# LC_EXT_SCH.net
KiCad netlist of a schematic drawn in Altium Designer
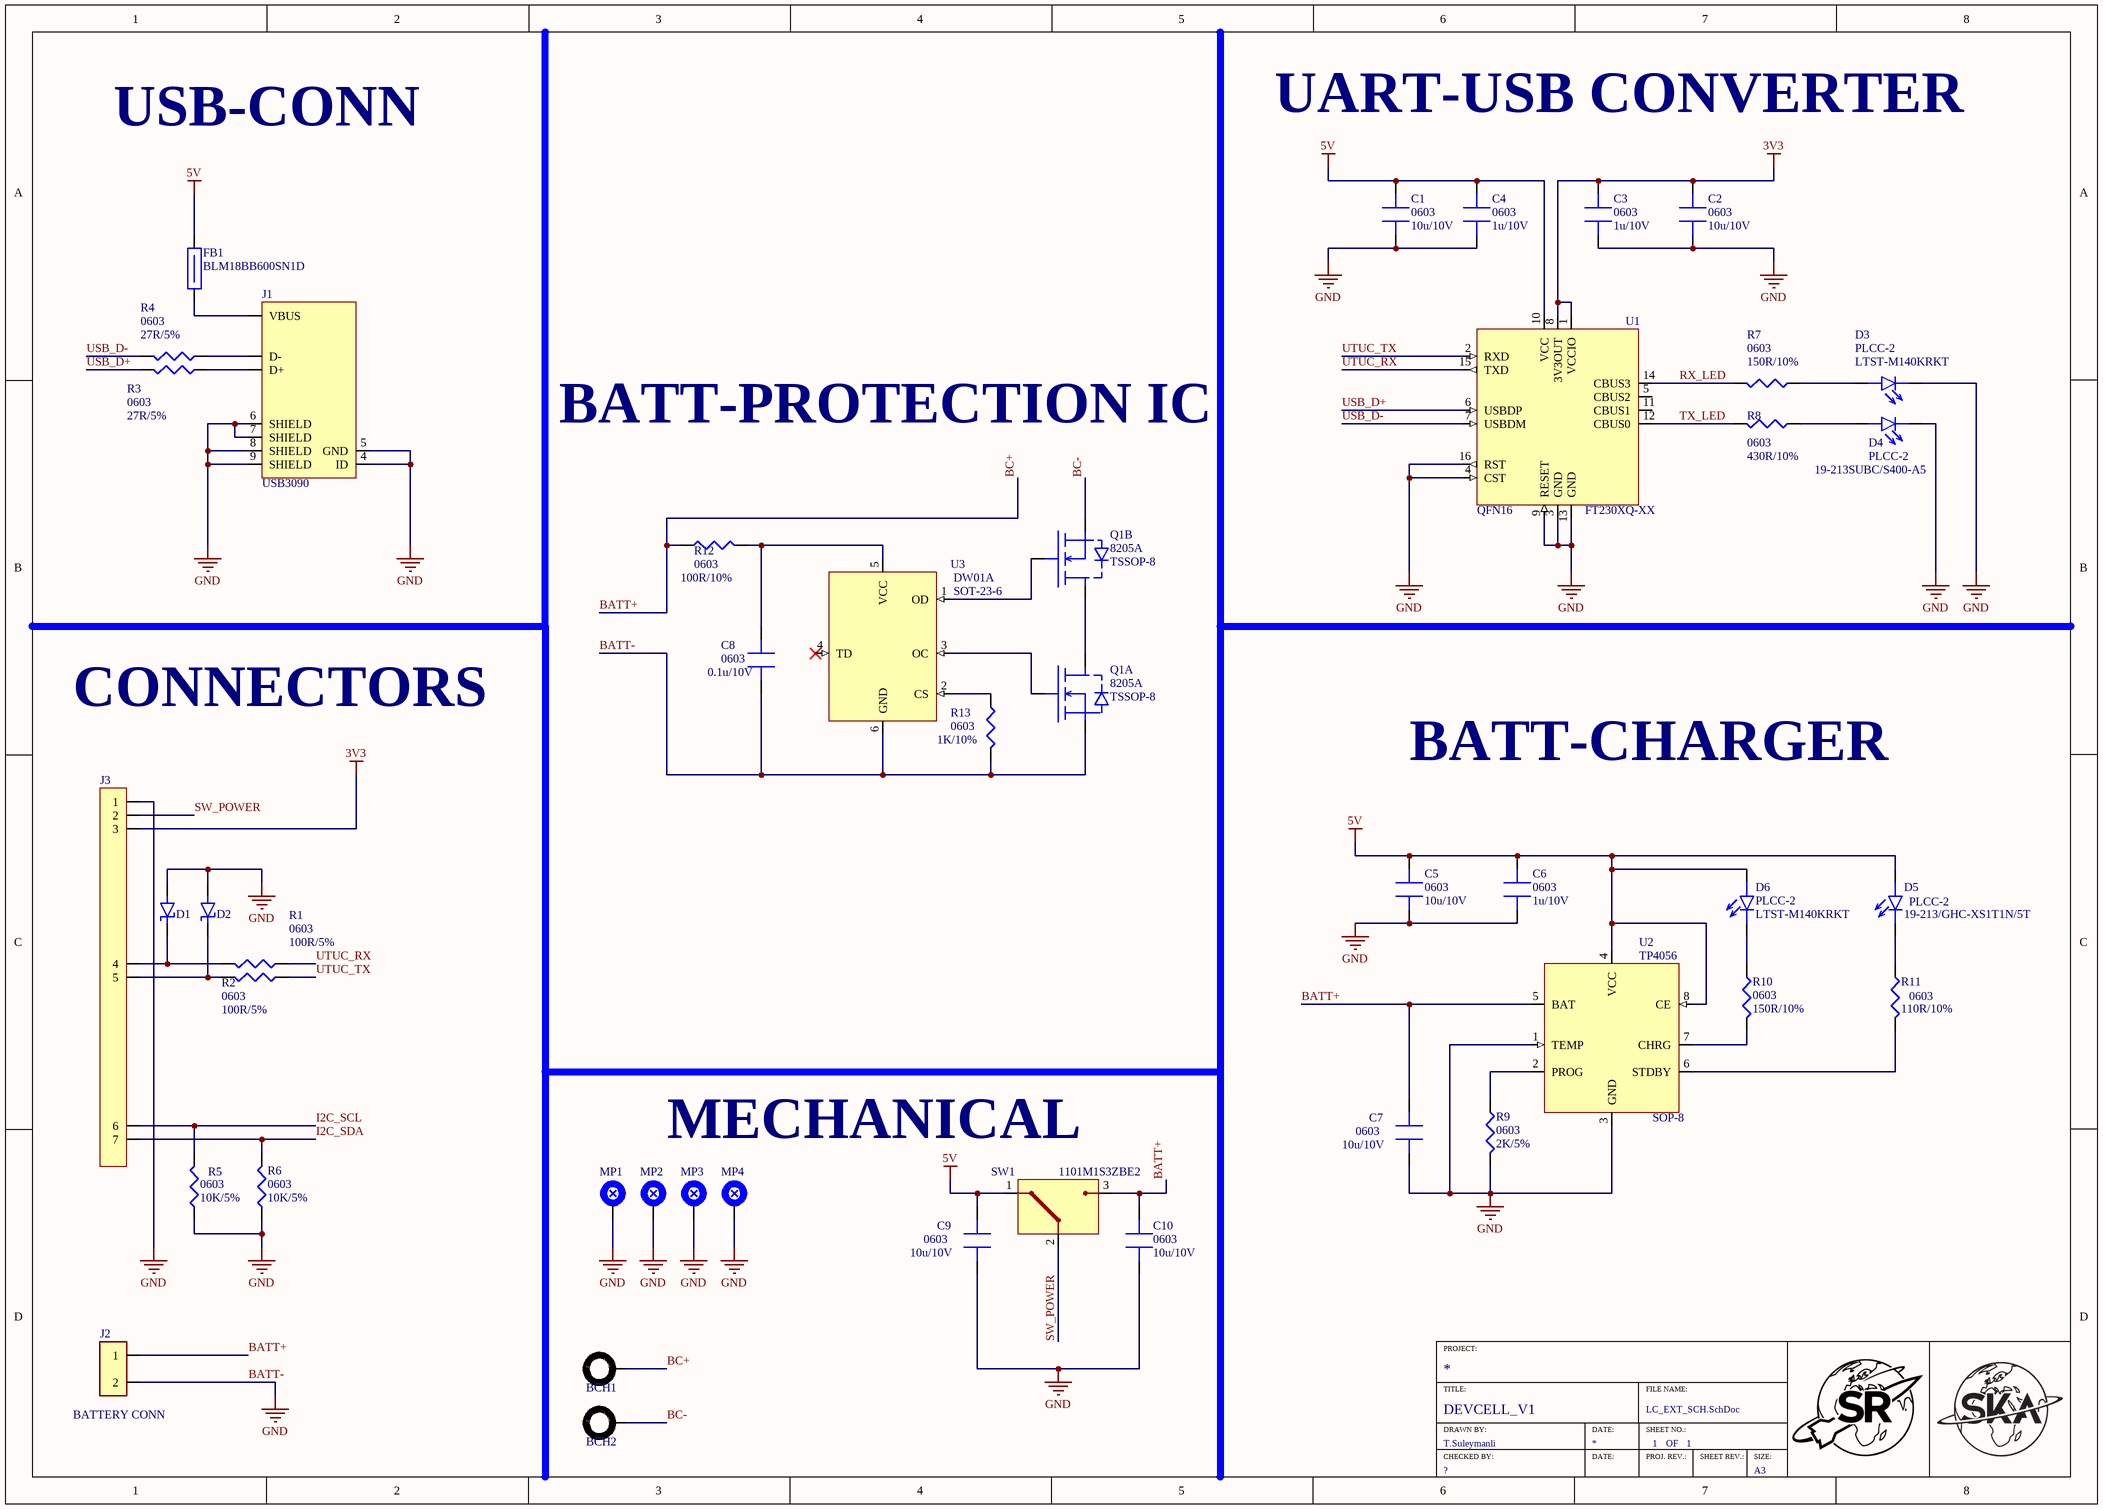
[diagram p0: LC_EXT_SCH.SchDoc]

(export (version "E")
  (design (tool "Eeschema 10.0.6"))
  (components
    (comp (ref "BCH1")
      (value "BATTERY_CONNECTION_HOLE")
      (footprint "BATTERY_CONN_HOLE")
      (description "Pin hole for battery connection")
      (libsource (lib "LC_EXT_S_lib") (part "BATTERY_CONNECTION_HOLE"))
    )
    (comp (ref "BCH2")
      (value "BATTERY_CONNECTION_HOLE")
      (footprint "BATTERY_CONN_HOLE")
      (description "Pin hole for battery connection")
      (libsource (lib "LC_EXT_S_lib") (part "BATTERY_CONNECTION_HOLE"))
    )
    (comp (ref "C1")
      (value "10u/10V")
      (footprint "CAPC1005X06L [0402]")
      (description "Standard capacitor")
      (fields (field (name "PACKAGE") "0603") (field (name "Comment") "C"))
      (libsource (lib "SR_Library") (part "C"))
    )
    (comp (ref "C2")
      (value "10u/10V")
      (footprint "CAPC1005X06L [0402]")
      (description "Standard capacitor")
      (fields (field (name "PACKAGE") "0603") (field (name "Comment") "C"))
      (libsource (lib "SR_Library") (part "C"))
    )
    (comp (ref "C3")
      (value "1u/10V")
      (footprint "CAPC1005X06L [0402]")
      (description "Standard capacitor")
      (fields (field (name "PACKAGE") "0603") (field (name "Comment") "C"))
      (libsource (lib "SR_Library") (part "C"))
    )
    (comp (ref "C4")
      (value "1u/10V")
      (footprint "CAPC1005X06L [0402]")
      (description "Standard capacitor")
      (fields (field (name "PACKAGE") "0603") (field (name "Comment") "C"))
      (libsource (lib "SR_Library") (part "C"))
    )
    (comp (ref "C5")
      (value "10u/10V")
      (footprint "CAPC1005X06L [0402]")
      (description "Standard capacitor")
      (fields (field (name "PACKAGE") "0603") (field (name "Comment") "C"))
      (libsource (lib "SR_Library") (part "C"))
    )
    (comp (ref "C6")
      (value "1u/10V")
      (footprint "CAPC1005X06L [0402]")
      (description "Standard capacitor")
      (fields (field (name "PACKAGE") "0603") (field (name "Comment") "C"))
      (libsource (lib "SR_Library") (part "C"))
    )
    (comp (ref "C7")
      (value "10u/10V")
      (footprint "CAPC1005X06L [0402]")
      (description "Standard capacitor")
      (fields (field (name "PACKAGE") "0603") (field (name "Comment") "C"))
      (libsource (lib "SR_Library") (part "C"))
    )
    (comp (ref "C8")
      (value "0.1u/10V")
      (footprint "CAPC1005X06L [0402]")
      (description "Standard capacitor")
      (fields (field (name "PACKAGE") "0603") (field (name "Comment") "C"))
      (libsource (lib "SR_Library") (part "C"))
    )
    (comp (ref "C9")
      (value "10u/10V")
      (footprint "CAPC1005X06L [0402]")
      (description "Standard capacitor")
      (fields (field (name "PACKAGE") "0603") (field (name "Comment") "C"))
      (libsource (lib "SR_Library") (part "C"))
    )
    (comp (ref "C10")
      (value "10u/10V")
      (footprint "CAPC1005X06L [0402]")
      (description "Standard capacitor")
      (fields (field (name "PACKAGE") "0603") (field (name "Comment") "C"))
      (libsource (lib "SR_Library") (part "C"))
    )
    (comp (ref "D1")
      (value "ESD5Z2.5T1G")
      (footprint "SODFL160X60-2N")
      (description "ESD protection diode, 4V")
      (libsource (lib "LC_EXT_S_lib") (part "D_Zener"))
    )
    (comp (ref "D2")
      (value "ESD5Z2.5T1G")
      (footprint "SODFL160X60-2N")
      (description "ESD protection diode, 4V")
      (libsource (lib "LC_EXT_S_lib") (part "D_Zener"))
    )
    (comp (ref "D3")
      (value "LTST-M140KRKT")
      (footprint "LEDC1608X35N")
      (description "LED; SMD; 3014; red; 0.24÷0.84lm; 90÷280mcd; 3x1.4x1.2mm; 120°; 20mA")
      (fields (field (name "PACKAGE") "PLCC-2") (field (name "PN") "LTST-M140KRKT"))
      (libsource (lib "SR_Library") (part "sLED"))
    )
    (comp (ref "D4")
      (value "19-213SUBC/S400-A5/S208-2/TR8")
      (footprint "19-213/GHC-XS1T1N/5T")
      (description "LED; SMD; blue; 10÷32mcd; 1.6x0.8x0.6mm; 120°; 2.7÷3.1V; 5mA; 40mW")
      (fields (field (name "PACKAGE") "PLCC-2") (field (name "PN") "19-213SUBC/S400-A5"))
      (libsource (lib "SR_Library") (part "sLED"))
    )
    (comp (ref "D5")
      (value "19-213/GHC-XS1T1N/5T")
      (footprint "19-213/GHC-XS1T1N/5T")
      (description "LED; SMD; 1608; green; 180÷360mcd; 1.6x0.8x0.6mm; 120°; 2.7÷3.7V")
      (fields (field (name "PACKAGE") "PLCC-2") (field (name "PN") "19-213/GHC-XS1T1N/5T"))
      (libsource (lib "SR_Library") (part "sLED"))
    )
    (comp (ref "D6")
      (value "LTST-M140KRKT")
      (footprint "LEDC1608X35N")
      (description "LED; SMD; 3014; red; 0.24÷0.84lm; 90÷280mcd; 3x1.4x1.2mm; 120°; 20mA")
      (fields (field (name "PACKAGE") "PLCC-2") (field (name "PN") "LTST-M140KRKT"))
      (libsource (lib "SR_Library") (part "sLED"))
    )
    (comp (ref "FB1")
      (value "BLM18BB600SN1D")
      (footprint "BEADC1608X95N")
      (description "Ferrite: bead; Imp.@ 100MHz: 60Ω; SMD; 0.55A; 0603; R: 0.25Ω")
      (libsource (lib "LC_EXT_S_lib") (part "Ferrite Bead"))
    )
    (comp (ref "J1")
      (value "USB3090")
      (footprint "USB3090-2888209")
      (description "USB Connectors Micro A/B Skt,Bottom-SMT, R/A, 30u No Peg, W/shell stake,T&R")
      (libsource (lib "LC_EXT_S_lib") (part "USB3090-30-A"))
    )
    (comp (ref "J2")
      (value "BATTERY CONN")
      (footprint "DG30825402P1400AH")
      (description "Standard battery connector for Li Ion battery")
      (libsource (lib "LC_EXT_S_lib") (part "BATTERY CONN"))
    )
    (comp (ref "J3")
      (value "Female_Header x7")
      (footprint "Female Header")
      (description "Header connectors x7 with 2.54 pitch")
      (libsource (lib "LC_EXT_S_lib") (part "Female_Header"))
    )
    (comp (ref "MP1")
      (value "Mounting hole")
      (footprint "Mounting_hole_M3")
      (libsource (lib "SR_Library") (part "Mounting hole"))
    )
    (comp (ref "MP2")
      (value "Mounting hole")
      (footprint "Mounting_hole_M3")
      (libsource (lib "SR_Library") (part "Mounting hole"))
    )
    (comp (ref "MP3")
      (value "Mounting hole")
      (footprint "Mounting_hole_M3")
      (libsource (lib "SR_Library") (part "Mounting hole"))
    )
    (comp (ref "MP4")
      (value "Mounting hole")
      (footprint "Mounting_hole_M3")
      (libsource (lib "SR_Library") (part "Mounting hole"))
    )
    (comp (ref "Q1")
      (value "8205A")
      (footprint "TSOP65P610X120-8M")
      (fields (field (name "PACKAGE") "TSSOP-8"))
      (libsource (lib "") (part "8205A_1"))
    )
    (comp (ref "R1")
      (value "100R/5%")
      (footprint "RESC1005X04L [0402]")
      (description "Standard resistor")
      (fields (field (name "PACKAGE") "0603") (field (name "Comment") "R"))
      (libsource (lib "SR_Library") (part "R"))
    )
    (comp (ref "R2")
      (value "100R/5%")
      (footprint "RESC1005X04L [0402]")
      (description "Standard resistor")
      (fields (field (name "PACKAGE") "0603") (field (name "Comment") "R"))
      (libsource (lib "SR_Library") (part "R"))
    )
    (comp (ref "R3")
      (value "27R/5%")
      (footprint "RESC1005X04L [0402]")
      (description "Standard resistor")
      (fields (field (name "PACKAGE") "0603") (field (name "Comment") "R"))
      (libsource (lib "SR_Library") (part "R"))
    )
    (comp (ref "R4")
      (value "27R/5%")
      (footprint "RESC1005X04L [0402]")
      (description "Standard resistor")
      (fields (field (name "PACKAGE") "0603") (field (name "Comment") "R"))
      (libsource (lib "SR_Library") (part "R"))
    )
    (comp (ref "R5")
      (value "10K/5%")
      (footprint "RESC1608X06M[0603]")
      (description "Standard resistor")
      (fields (field (name "PACKAGE") "0603") (field (name "Comment") "R"))
      (libsource (lib "SR_Library") (part "R"))
    )
    (comp (ref "R6")
      (value "10K/5%")
      (footprint "RESC1608X06M[0603]")
      (description "Standard resistor")
      (fields (field (name "PACKAGE") "0603") (field (name "Comment") "R"))
      (libsource (lib "SR_Library") (part "R"))
    )
    (comp (ref "R7")
      (value "150R/10%")
      (footprint "RESC1005X04L [0402]")
      (description "Standard resistor")
      (fields (field (name "PACKAGE") "0603") (field (name "Comment") "R"))
      (libsource (lib "SR_Library") (part "R"))
    )
    (comp (ref "R8")
      (value "430R/10%")
      (footprint "RESC1005X04L [0402]")
      (description "Standard resistor")
      (fields (field (name "PACKAGE") "0603") (field (name "Comment") "R"))
      (libsource (lib "SR_Library") (part "R"))
    )
    (comp (ref "R9")
      (value "2K/5%")
      (footprint "RESC1005X04L [0402]")
      (description "Standard resistor")
      (fields (field (name "PACKAGE") "0603") (field (name "Comment") "R"))
      (libsource (lib "SR_Library") (part "R"))
    )
    (comp (ref "R10")
      (value "150R/10%")
      (footprint "RESC1005X04L [0402]")
      (description "Standard resistor")
      (fields (field (name "PACKAGE") "0603") (field (name "Comment") "R"))
      (libsource (lib "SR_Library") (part "R"))
    )
    (comp (ref "R11")
      (value "110R/10%")
      (footprint "RESC1005X04L [0402]")
      (description "Standard resistor")
      (fields (field (name "PACKAGE") "0603") (field (name "Comment") "R"))
      (libsource (lib "SR_Library") (part "R"))
    )
    (comp (ref "R12")
      (value "100R/10%")
      (footprint "RESC1005X04L [0402]")
      (description "Standard resistor")
      (fields (field (name "PACKAGE") "0603") (field (name "Comment") "R"))
      (libsource (lib "SR_Library") (part "R"))
    )
    (comp (ref "R13")
      (value "1K/10%")
      (footprint "RESC1005X04L [0402]")
      (description "Standard resistor")
      (fields (field (name "PACKAGE") "0603") (field (name "Comment") "R"))
      (libsource (lib "SR_Library") (part "R"))
    )
    (comp (ref "SW1")
      (value "1101M1S3ZBE2")
      (footprint "1101M1S3ZBE2")
      (description "Switch: slide; Pos: 2; SPDT; 0.02A/20VAC; 0.02A/20VDC; ON-ON; 1000")
      (libsource (lib "LC_EXT_S_lib") (part "1101M1S3ZBE2"))
    )
    (comp (ref "U1")
      (value "FT230XQ-XX")
      (footprint "QFN65P400X400X75_HS-17N")
      (description "USB Interface IC USB to Basic Serial UART IC QFN-16")
      (fields (field (name "PACKAGE") "QFN16"))
      (libsource (lib "LC_EXT_S_lib") (part "FT230XQ-T"))
    )
    (comp (ref "U2")
      (value "TP4056")
      (footprint "SOP127P600X170-8N")
      (description "1A Standalone Linear Li-lon Battery Charger with Thermal\r\nRegulation")
      (fields (field (name "PACKAGE") "SOP-8"))
      (libsource (lib "LC_EXT_S_lib") (part "TP4056-42-SOP8-PP"))
    )
    (comp (ref "U3")
      (value "DW01A")
      (footprint "SOT95P270X145-6M")
      (description "Battery protection IC, SOT-23-6, 4.3V± 50mV, -40°C ~ +85°C")
      (fields (field (name "PACKAGE") "SOT-23-6"))
      (libsource (lib "LC_EXT_S_lib") (part "DW01A"))
    )
  )
  (nets
    (net (code "1") (name "/BATT+") (class "Default")
      (node (ref "BCH1") (pin "1") (pinfunction "1_1") (pintype "passive"))
      (node (ref "C10") (pin "1") (pinfunction "1_1") (pintype "passive"))
      (node (ref "C7") (pin "1") (pinfunction "1_1") (pintype "passive"))
      (node (ref "J2") (pin "1") (pinfunction "1_1") (pintype "passive"))
      (node (ref "R12") (pin "2") (pinfunction "2_2") (pintype "passive"))
      (node (ref "SW1") (pin "3") (pinfunction "BATT+_3") (pintype "passive"))
      (node (ref "U2") (pin "5") (pinfunction "BAT_5") (pintype "passive"))
    )
    (net (code "2") (name "/BC-") (class "Default")
      (node (ref "BCH2") (pin "1") (pinfunction "1_1") (pintype "passive"))
      (node (ref "Q1") (pin "7") (pinfunction "S2_7") (pintype "passive"))
    )
    (net (code "3") (name "/I2C_SCL") (class "Default")
      (node (ref "J3") (pin "6") (pinfunction "6_6") (pintype "passive"))
      (node (ref "R5") (pin "1") (pinfunction "1_1") (pintype "passive"))
    )
    (net (code "4") (name "/I2C_SDA") (class "Default")
      (node (ref "J3") (pin "7") (pinfunction "7_7") (pintype "passive"))
      (node (ref "R6") (pin "1") (pinfunction "1_1") (pintype "passive"))
    )
    (net (code "5") (name "/RX_LED") (class "Default")
      (node (ref "R7") (pin "1") (pinfunction "1_1") (pintype "passive"))
      (node (ref "U1") (pin "14") (pinfunction "CBUS3_14") (pintype "bidirectional"))
    )
    (net (code "6") (name "/SW_POWER") (class "Default")
      (node (ref "J3") (pin "2") (pinfunction "2_2") (pintype "passive"))
      (node (ref "SW1") (pin "2") (pinfunction "COM_2") (pintype "passive"))
    )
    (net (code "7") (name "/TX_LED") (class "Default")
      (node (ref "R8") (pin "1") (pinfunction "1_1") (pintype "passive"))
      (node (ref "U1") (pin "12") (pinfunction "CBUS0_12") (pintype "bidirectional"))
    )
    (net (code "8") (name "/USB_D+") (class "Default")
      (node (ref "R3") (pin "1") (pinfunction "1_1") (pintype "passive"))
      (node (ref "U1") (pin "6") (pinfunction "USBDP_6") (pintype "input"))
    )
    (net (code "9") (name "/USB_D-") (class "Default")
      (node (ref "R4") (pin "1") (pinfunction "1_1") (pintype "passive"))
      (node (ref "U1") (pin "7") (pinfunction "USBDM_7") (pintype "input"))
    )
    (net (code "10") (name "/UTUC_RX") (class "Default")
      (node (ref "R1") (pin "2") (pinfunction "2_2") (pintype "passive"))
      (node (ref "U1") (pin "15") (pinfunction "TXD_15") (pintype "output"))
    )
    (net (code "11") (name "/UTUC_TX") (class "Default")
      (node (ref "R2") (pin "2") (pinfunction "2_2") (pintype "passive"))
      (node (ref "U1") (pin "2") (pinfunction "RXD_2") (pintype "input"))
    )
    (net (code "12") (name "3V3") (class "Default")
      (node (ref "C2") (pin "1") (pinfunction "1_1") (pintype "passive"))
      (node (ref "C3") (pin "1") (pinfunction "1_1") (pintype "passive"))
      (node (ref "J3") (pin "3") (pinfunction "3_3") (pintype "passive"))
      (node (ref "U1") (pin "1") (pinfunction "VCCIO_1") (pintype "passive"))
      (node (ref "U1") (pin "8") (pinfunction "3V3OUT_8") (pintype "passive"))
    )
    (net (code "13") (name "5V") (class "Default")
      (node (ref "C1") (pin "1") (pinfunction "1_1") (pintype "passive"))
      (node (ref "C4") (pin "1") (pinfunction "1_1") (pintype "passive"))
      (node (ref "C5") (pin "1") (pinfunction "1_1") (pintype "passive"))
      (node (ref "C6") (pin "1") (pinfunction "1_1") (pintype "passive"))
      (node (ref "C9") (pin "1") (pinfunction "1_1") (pintype "passive"))
      (node (ref "D5") (pin "2") (pinfunction "2_2") (pintype "passive"))
      (node (ref "D6") (pin "2") (pinfunction "2_2") (pintype "passive"))
      (node (ref "FB1") (pin "2") (pinfunction "2_2") (pintype "passive"))
      (node (ref "SW1") (pin "1") (pinfunction "5V_1") (pintype "passive"))
      (node (ref "U1") (pin "10") (pinfunction "VCC_10") (pintype "passive"))
      (node (ref "U2") (pin "4") (pinfunction "VCC_4") (pintype "passive"))
      (node (ref "U2") (pin "8") (pinfunction "CE_8") (pintype "input"))
    )
    (net (code "14") (name "GND") (class "Default")
      (node (ref "C1") (pin "2") (pinfunction "2_2") (pintype "passive"))
      (node (ref "C10") (pin "2") (pinfunction "2_2") (pintype "passive"))
      (node (ref "C2") (pin "2") (pinfunction "2_2") (pintype "passive"))
      (node (ref "C3") (pin "2") (pinfunction "2_2") (pintype "passive"))
      (node (ref "C4") (pin "2") (pinfunction "2_2") (pintype "passive"))
      (node (ref "C5") (pin "2") (pinfunction "2_2") (pintype "passive"))
      (node (ref "C6") (pin "2") (pinfunction "2_2") (pintype "passive"))
      (node (ref "C7") (pin "2") (pinfunction "2_2") (pintype "passive"))
      (node (ref "C8") (pin "2") (pinfunction "2_2") (pintype "passive"))
      (node (ref "C9") (pin "2") (pinfunction "2_2") (pintype "passive"))
      (node (ref "D1") (pin "2") (pinfunction "A_2") (pintype "passive"))
      (node (ref "D2") (pin "2") (pinfunction "A_2") (pintype "passive"))
      (node (ref "D3") (pin "1") (pinfunction "1_1") (pintype "passive"))
      (node (ref "D4") (pin "1") (pinfunction "1_1") (pintype "passive"))
      (node (ref "J1") (pin "4") (pinfunction "ID_4") (pintype "passive"))
      (node (ref "J1") (pin "5") (pinfunction "GND_5") (pintype "passive"))
      (node (ref "J1") (pin "6") (pinfunction "SHIELD_6") (pintype "passive"))
      (node (ref "J1") (pin "7") (pinfunction "SHIELD_7") (pintype "passive"))
      (node (ref "J1") (pin "8") (pinfunction "SHIELD_8") (pintype "passive"))
      (node (ref "J1") (pin "9") (pinfunction "SHIELD_9") (pintype "passive"))
      (node (ref "J2") (pin "2") (pinfunction "2_2") (pintype "passive"))
      (node (ref "J3") (pin "1") (pinfunction "1_1") (pintype "passive"))
      (node (ref "MP1") (pin "1") (pinfunction "1_1") (pintype "passive"))
      (node (ref "MP2") (pin "1") (pinfunction "1_1") (pintype "passive"))
      (node (ref "MP3") (pin "1") (pinfunction "1_1") (pintype "passive"))
      (node (ref "MP4") (pin "1") (pinfunction "1_1") (pintype "passive"))
      (node (ref "Q1") (pin "2") (pinfunction "S1_2") (pintype "passive"))
      (node (ref "R13") (pin "1") (pinfunction "1_1") (pintype "passive"))
      (node (ref "R5") (pin "2") (pinfunction "2_2") (pintype "passive"))
      (node (ref "R6") (pin "2") (pinfunction "2_2") (pintype "passive"))
      (node (ref "R9") (pin "1") (pinfunction "1_1") (pintype "passive"))
      (node (ref "U1") (pin "13") (pinfunction "GND_13") (pintype "passive"))
      (node (ref "U1") (pin "16") (pinfunction "RST_16") (pintype "output"))
      (node (ref "U1") (pin "3") (pinfunction "GND_3") (pintype "passive"))
      (node (ref "U1") (pin "4") (pinfunction "CST_4") (pintype "input"))
      (node (ref "U1") (pin "9") (pinfunction "RESET_9") (pintype "input"))
      (node (ref "U2") (pin "1") (pinfunction "TEMP_1") (pintype "input"))
      (node (ref "U2") (pin "3") (pinfunction "GND_3") (pintype "passive"))
      (node (ref "U3") (pin "6") (pinfunction "GND_6") (pintype "passive"))
    )
    (net (code "15") (name "Net-(D1-C)") (class "Default")
      (node (ref "D1") (pin "1") (pinfunction "C_1") (pintype "passive"))
      (node (ref "J3") (pin "4") (pinfunction "4_4") (pintype "passive"))
      (node (ref "R1") (pin "1") (pinfunction "1_1") (pintype "passive"))
    )
    (net (code "16") (name "Net-(D2-C)") (class "Default")
      (node (ref "D2") (pin "1") (pinfunction "C_1") (pintype "passive"))
      (node (ref "J3") (pin "5") (pinfunction "5_5") (pintype "passive"))
      (node (ref "R2") (pin "1") (pinfunction "1_1") (pintype "passive"))
    )
    (net (code "17") (name "Net-(D3-Pad2)") (class "Default")
      (node (ref "D3") (pin "2") (pinfunction "2_2") (pintype "passive"))
      (node (ref "R7") (pin "2") (pinfunction "2_2") (pintype "passive"))
    )
    (net (code "18") (name "Net-(D4-Pad2)") (class "Default")
      (node (ref "D4") (pin "2") (pinfunction "2_2") (pintype "passive"))
      (node (ref "R8") (pin "2") (pinfunction "2_2") (pintype "passive"))
    )
    (net (code "19") (name "Net-(D5-Pad1)") (class "Default")
      (node (ref "D5") (pin "1") (pinfunction "1_1") (pintype "passive"))
      (node (ref "R11") (pin "2") (pinfunction "2_2") (pintype "passive"))
    )
    (net (code "20") (name "Net-(D6-Pad1)") (class "Default")
      (node (ref "D6") (pin "1") (pinfunction "1_1") (pintype "passive"))
      (node (ref "R10") (pin "2") (pinfunction "2_2") (pintype "passive"))
    )
    (net (code "21") (name "Net-(J1-D+)") (class "Default")
      (node (ref "J1") (pin "3") (pinfunction "D+_3") (pintype "bidirectional"))
      (node (ref "R3") (pin "2") (pinfunction "2_2") (pintype "passive"))
    )
    (net (code "22") (name "Net-(J1-D-)") (class "Default")
      (node (ref "J1") (pin "2") (pinfunction "D-_2") (pintype "bidirectional"))
      (node (ref "R4") (pin "2") (pinfunction "2_2") (pintype "passive"))
    )
    (net (code "23") (name "Net-(J1-VBUS)") (class "Default")
      (node (ref "FB1") (pin "1") (pinfunction "1_1") (pintype "passive"))
      (node (ref "J1") (pin "1") (pinfunction "VBUS_1") (pintype "power_in"))
    )
    (net (code "24") (name "Net-(Q1A-D1)") (class "Default")
      (node (ref "Q1") (pin "1") (pinfunction "D1_1") (pintype "passive"))
      (node (ref "Q1") (pin "8") (pinfunction "D2_8") (pintype "passive"))
    )
    (net (code "25") (name "Net-(Q1A-G1)") (class "Default")
      (node (ref "Q1") (pin "4") (pinfunction "G1_4") (pintype "passive"))
      (node (ref "U3") (pin "3") (pinfunction "OC_3") (pintype "input"))
    )
    (net (code "26") (name "Net-(Q1B-G2)") (class "Default")
      (node (ref "Q1") (pin "5") (pinfunction "G2_5") (pintype "passive"))
      (node (ref "U3") (pin "1") (pinfunction "OD_1") (pintype "input"))
    )
    (net (code "27") (name "Net-(U2-CHRG)") (class "Default")
      (node (ref "R10") (pin "1") (pinfunction "1_1") (pintype "passive"))
      (node (ref "U2") (pin "7") (pinfunction "CHRG_7") (pintype "passive"))
    )
    (net (code "28") (name "Net-(U2-PROG)") (class "Default")
      (node (ref "R9") (pin "2") (pinfunction "2_2") (pintype "passive"))
      (node (ref "U2") (pin "2") (pinfunction "PROG_2") (pintype "passive"))
    )
    (net (code "29") (name "Net-(U2-STDBY)") (class "Default")
      (node (ref "R11") (pin "1") (pinfunction "1_1") (pintype "passive"))
      (node (ref "U2") (pin "6") (pinfunction "STDBY_6") (pintype "passive"))
    )
    (net (code "30") (name "Net-(U3-CS)") (class "Default")
      (node (ref "R13") (pin "2") (pinfunction "2_2") (pintype "passive"))
      (node (ref "U3") (pin "2") (pinfunction "CS_2") (pintype "input"))
    )
    (net (code "31") (name "Net-(U3-VCC)") (class "Default")
      (node (ref "C8") (pin "1") (pinfunction "1_1") (pintype "passive"))
      (node (ref "R12") (pin "1") (pinfunction "1_1") (pintype "passive"))
      (node (ref "U3") (pin "5") (pinfunction "VCC_5") (pintype "passive"))
    )
    (net (code "32") (name "unconnected-(U1-CBUS1-Pad11)") (class "Default")
      (node (ref "U1") (pin "11") (pinfunction "CBUS1_11") (pintype "bidirectional"))
    )
    (net (code "33") (name "unconnected-(U1-CBUS2-Pad5)") (class "Default")
      (node (ref "U1") (pin "5") (pinfunction "CBUS2_5") (pintype "bidirectional"))
    )
    (net (code "34") (name "unconnected-(U3-TD-Pad4)") (class "Default")
      (node (ref "U3") (pin "4") (pinfunction "TD_4") (pintype "input+no_connect"))
    )
  )
)
